# PWM.net
KiCad netlist of a schematic drawn in EAGLE
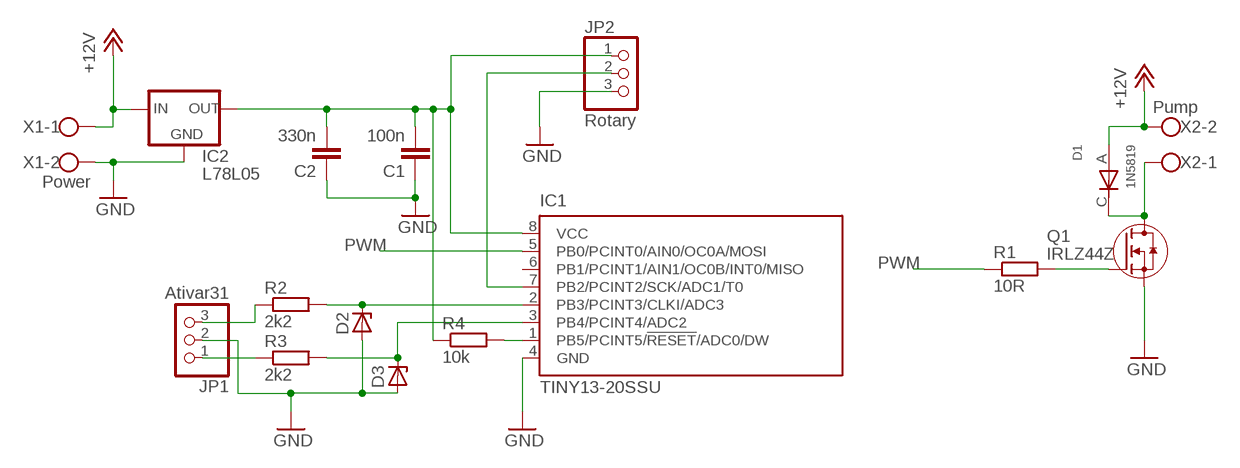
[diagram p0: schematic, sheet 1]

(export (version "E")
  (design (tool "Eeschema 10.0.6"))
  (components
    (comp (ref "C1")
      (value "100n")
      (footprint "eagle-import:C0805")
      (libsource (lib "eagle-import") (part "C-EUC0805"))
    )
    (comp (ref "C2")
      (value "330n")
      (footprint "eagle-import:C0805")
      (libsource (lib "eagle-import") (part "C-EUC0805"))
    )
    (comp (ref "D1")
      (value "1N5819")
      (footprint "eagle-import:DO214AC")
      (libsource (lib "eagle-import") (part "DIODESMD"))
    )
    (comp (ref "D2")
      (value "ZENER-DIODESOD80C")
      (footprint "eagle-import:SOD80C")
      (libsource (lib "eagle-import") (part "ZENER-DIODESOD80C"))
    )
    (comp (ref "D3")
      (value "ZENER-DIODESOD80C")
      (footprint "eagle-import:SOD80C")
      (libsource (lib "eagle-import") (part "ZENER-DIODESOD80C"))
    )
    (comp (ref "IC1")
      (value "TINY13-20SSU")
      (footprint "eagle-import:8S1")
      (fields (field (name "MPN") "ATTINY13-20SSU"))
      (libsource (lib "eagle-import") (part "TINY13SSU-20"))
    )
    (comp (ref "IC2")
      (value "L78L05")
      (footprint "eagle-import:78LXX")
      (libsource (lib "eagle-import") (part "78LXX"))
    )
    (comp (ref "JP1")
      (value "Ativar31")
      (footprint "eagle-import:1X03")
      (libsource (lib "eagle-import") (part "PINHD-1X3"))
    )
    (comp (ref "JP2")
      (value "Rotary")
      (footprint "eagle-import:1X03")
      (libsource (lib "eagle-import") (part "PINHD-1X3"))
    )
    (comp (ref "Q1")
      (value "IRLZ44Z")
      (footprint "eagle-import:TO220AV")
      (libsource (lib "eagle-import") (part "IRLZ44Z"))
    )
    (comp (ref "R1")
      (value "10R")
      (footprint "eagle-import:R0805")
      (libsource (lib "eagle-import") (part "R-EU_R0805"))
    )
    (comp (ref "R2")
      (value "2k2")
      (footprint "eagle-import:R0805")
      (libsource (lib "eagle-import") (part "R-EU_R0805"))
    )
    (comp (ref "R3")
      (value "2k2")
      (footprint "eagle-import:R0805")
      (libsource (lib "eagle-import") (part "R-EU_R0805"))
    )
    (comp (ref "R4")
      (value "10k")
      (footprint "eagle-import:R0805")
      (libsource (lib "eagle-import") (part "R-EU_R0805"))
    )
    (comp (ref "X1")
      (value "Power")
      (footprint "eagle-import:W237-102")
      (fields (field (name "MPN") "237-102"))
      (libsource (lib "eagle-import") (part "W237-102"))
    )
    (comp (ref "X2")
      (value "Pump")
      (footprint "eagle-import:W237-102")
      (fields (field (name "MPN") "237-102"))
      (libsource (lib "eagle-import") (part "W237-102"))
    )
  )
  (nets
    (net (code "1") (name "+12V") (class "Default")
      (node (ref "D1") (pin "A") (pinfunction "ANOD_A") (pintype "power_in"))
      (node (ref "IC2") (pin "IN") (pinfunction "IN_IN") (pintype "input"))
      (node (ref "X1") (pin "1") (pinfunction "KL_1") (pintype "passive"))
      (node (ref "X2") (pin "2") (pinfunction "KL_2") (pintype "passive"))
    )
    (net (code "2") (name "/PWM") (class "Default")
      (node (ref "IC1") (pin "5") (pinfunction "PB0/PCINT0/AIN0/OC0A/MOSI_5") (pintype "bidirectional"))
      (node (ref "R1") (pin "1") (pinfunction "1_1") (pintype "passive"))
    )
    (net (code "3") (name "GND") (class "Default")
      (node (ref "C1") (pin "1") (pinfunction "1_1") (pintype "passive"))
      (node (ref "C2") (pin "1") (pinfunction "1_1") (pintype "passive"))
      (node (ref "D2") (pin "A") (pinfunction "A_A") (pintype "passive"))
      (node (ref "D3") (pin "A") (pinfunction "A_A") (pintype "passive"))
      (node (ref "IC1") (pin "4") (pinfunction "GND_4") (pintype "power_in"))
      (node (ref "IC2") (pin "GND") (pinfunction "GND_GND") (pintype "input"))
      (node (ref "JP1") (pin "2") (pinfunction "2_2") (pintype "passive"))
      (node (ref "JP2") (pin "3") (pinfunction "3_3") (pintype "passive"))
      (node (ref "Q1") (pin "3") (pinfunction "S_3") (pintype "passive"))
      (node (ref "X1") (pin "2") (pinfunction "KL_2") (pintype "passive"))
    )
    (net (code "4") (name "Net-(D1-KATOD)") (class "Default")
      (node (ref "D1") (pin "C") (pinfunction "KATOD_C") (pintype "power_in"))
      (node (ref "Q1") (pin "2") (pinfunction "D_2") (pintype "passive"))
      (node (ref "X2") (pin "1") (pinfunction "KL_1") (pintype "passive"))
    )
    (net (code "5") (name "Net-(IC1-PB2{slash}PCINT2{slash}SCK{slash}ADC1{slash}T0)") (class "Default")
      (node (ref "IC1") (pin "7") (pinfunction "PB2/PCINT2/SCK/ADC1/T0_7") (pintype "bidirectional"))
      (node (ref "JP2") (pin "2") (pinfunction "2_2") (pintype "passive"))
    )
    (net (code "6") (name "Net-(IC1-PB3{slash}PCINT3{slash}CLKI{slash}ADC3)") (class "Default")
      (node (ref "D2") (pin "C") (pinfunction "C_C") (pintype "passive"))
      (node (ref "IC1") (pin "2") (pinfunction "PB3/PCINT3/CLKI/ADC3_2") (pintype "bidirectional"))
      (node (ref "R2") (pin "2") (pinfunction "2_2") (pintype "passive"))
    )
    (net (code "7") (name "Net-(IC1-PB4{slash}PCINT4{slash}ADC2)") (class "Default")
      (node (ref "D3") (pin "C") (pinfunction "C_C") (pintype "passive"))
      (node (ref "IC1") (pin "3") (pinfunction "PB4/PCINT4/ADC2_3") (pintype "bidirectional"))
      (node (ref "R3") (pin "2") (pinfunction "2_2") (pintype "passive"))
    )
    (net (code "8") (name "Net-(IC1-PB5{slash}PCINT5{slash}~{RESET}{slash}ADC0{slash}DW)") (class "Default")
      (node (ref "IC1") (pin "1") (pinfunction "PB5/PCINT5/~{RESET}/ADC0/DW_1") (pintype "bidirectional"))
      (node (ref "R4") (pin "2") (pinfunction "2_2") (pintype "passive"))
    )
    (net (code "9") (name "Net-(IC1-VCC)") (class "Default")
      (node (ref "C1") (pin "2") (pinfunction "2_2") (pintype "passive"))
      (node (ref "C2") (pin "2") (pinfunction "2_2") (pintype "passive"))
      (node (ref "IC1") (pin "8") (pinfunction "VCC_8") (pintype "power_in"))
      (node (ref "IC2") (pin "OUT") (pinfunction "OUT_OUT") (pintype "passive"))
      (node (ref "JP2") (pin "1") (pinfunction "1_1") (pintype "passive"))
      (node (ref "R4") (pin "1") (pinfunction "1_1") (pintype "passive"))
    )
    (net (code "10") (name "Net-(JP1-Pad1)") (class "Default")
      (node (ref "JP1") (pin "1") (pinfunction "1_1") (pintype "passive"))
      (node (ref "R3") (pin "1") (pinfunction "1_1") (pintype "passive"))
    )
    (net (code "11") (name "Net-(JP1-Pad3)") (class "Default")
      (node (ref "JP1") (pin "3") (pinfunction "3_3") (pintype "passive"))
      (node (ref "R2") (pin "1") (pinfunction "1_1") (pintype "passive"))
    )
    (net (code "12") (name "Net-(Q1-G)") (class "Default")
      (node (ref "Q1") (pin "1") (pinfunction "G_1") (pintype "passive"))
      (node (ref "R1") (pin "2") (pinfunction "2_2") (pintype "passive"))
    )
    (net (code "13") (name "unconnected-(IC1-PB1{slash}PCINT1{slash}AIN1{slash}OC0B{slash}INT0{slash}MISO-Pad6)") (class "Default")
      (node (ref "IC1") (pin "6") (pinfunction "PB1/PCINT1/AIN1/OC0B/INT0/MISO_6") (pintype "bidirectional"))
    )
  )
)
